# design.net
KiCad netlist of a schematic drawn in Altium Designer
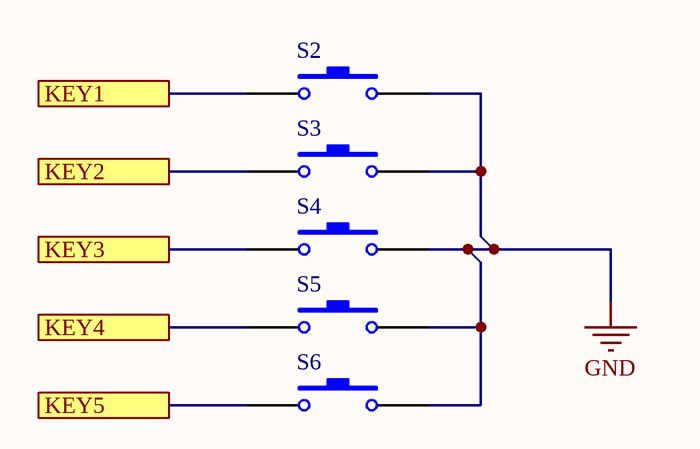
[diagram p0: 按键电路.SchDoc]

(export (version "E")
  (design (tool "Eeschema 10.0.6"))
  (components
    (comp (ref "S2")
      (value "KEY")
      (footprint "SW-MINI")
      (description "Switch")
      (fields (field (name "PUBLISHER") "Altium Limited"))
      (libsource (lib "基于SMT32的DDS信号源原理图库") (part "SW-PB"))
    )
    (comp (ref "S3")
      (value "KEY")
      (footprint "SW-MINI")
      (description "Switch")
      (fields (field (name "PUBLISHER") "Altium Limited"))
      (libsource (lib "基于SMT32的DDS信号源原理图库") (part "SW-PB"))
    )
    (comp (ref "S4")
      (value "KEY")
      (footprint "SW-MINI")
      (description "Switch")
      (fields (field (name "PUBLISHER") "Altium Limited"))
      (libsource (lib "基于SMT32的DDS信号源原理图库") (part "SW-PB"))
    )
    (comp (ref "S5")
      (value "KEY")
      (footprint "SW-MINI")
      (description "Switch")
      (fields (field (name "PUBLISHER") "Altium Limited"))
      (libsource (lib "基于SMT32的DDS信号源原理图库") (part "SW-PB"))
    )
    (comp (ref "S6")
      (value "KEY")
      (footprint "SW-MINI")
      (description "Switch")
      (fields (field (name "PUBLISHER") "Altium Limited"))
      (libsource (lib "基于SMT32的DDS信号源原理图库") (part "SW-PB"))
    )
  )
  (nets
    (net (code "1") (name "/KEY1") (class "Default")
      (node (ref "S2") (pin "1") (pinfunction "1_1") (pintype "passive"))
    )
    (net (code "2") (name "/KEY2") (class "Default")
      (node (ref "S3") (pin "1") (pinfunction "1_1") (pintype "passive"))
    )
    (net (code "3") (name "/KEY3") (class "Default")
      (node (ref "S4") (pin "1") (pinfunction "1_1") (pintype "passive"))
    )
    (net (code "4") (name "/KEY4") (class "Default")
      (node (ref "S5") (pin "1") (pinfunction "1_1") (pintype "passive"))
    )
    (net (code "5") (name "/KEY5") (class "Default")
      (node (ref "S6") (pin "1") (pinfunction "1_1") (pintype "passive"))
    )
    (net (code "6") (name "GND") (class "Default")
      (node (ref "S2") (pin "2") (pinfunction "2_2") (pintype "passive"))
      (node (ref "S3") (pin "2") (pinfunction "2_2") (pintype "passive"))
      (node (ref "S4") (pin "2") (pinfunction "2_2") (pintype "passive"))
      (node (ref "S5") (pin "2") (pinfunction "2_2") (pintype "passive"))
      (node (ref "S6") (pin "2") (pinfunction "2_2") (pintype "passive"))
    )
  )
)
